# JN5168_Breakout.net
KiCad netlist of a schematic drawn in EAGLE
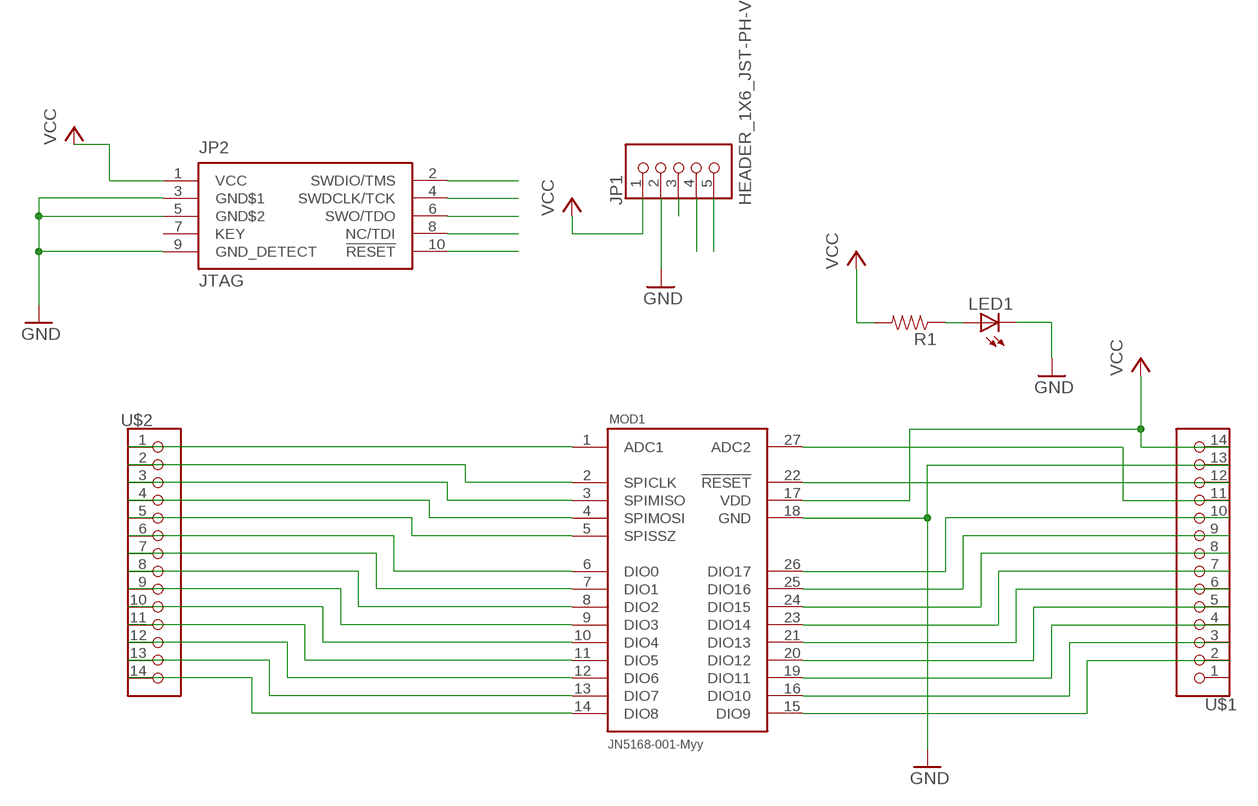
[diagram p0: schematic, sheet 1]

(export (version "E")
  (design (tool "Eeschema 10.0.6"))
  (components
    (comp (ref "JP1")
      (value "HEADER_1X6_JST-PH-V")
      (footprint "eagle-import:HEADER_100MIL_1X5")
      (libsource (lib "eagle-import") (part "HEADER_1X5100MIL_PTH"))
    )
    (comp (ref "JP2")
      (value "JTAG_HEADER")
      (footprint "eagle-import:HEADER_50MIL_2X5_PTH")
      (libsource (lib "eagle-import") (part "JTAG_HEADER"))
    )
    (comp (ref "LED1")
      (value "LEDCHIPLED_0603")
      (footprint "eagle-import:CHIPLED_0603")
      (libsource (lib "eagle-import") (part "LEDCHIPLED_0603"))
    )
    (comp (ref "MOD1")
      (value "JN5168-001-M00")
      (footprint "eagle-import:JN5168-001-M00")
      (libsource (lib "eagle-import") (part "JN5168-001-M00"))
    )
    (comp (ref "R1")
      (value "R0603")
      (footprint "eagle-import:R0603")
      (libsource (lib "eagle-import") (part "R0603"))
    )
    (comp (ref "U$1")
      (value "HEADER_1X14_100MIL_PTH")
      (footprint "eagle-import:HEADER_100MIL_1X14_PTH")
      (libsource (lib "eagle-import") (part "HEADER_1X14_100MIL_PTH"))
    )
    (comp (ref "U$2")
      (value "HEADER_1X14_100MIL_PTH")
      (footprint "eagle-import:HEADER_100MIL_1X14_PTH")
      (libsource (lib "eagle-import") (part "HEADER_1X14_100MIL_PTH"))
    )
  )
  (nets
    (net (code "1") (name "/GPIO4{slash}JTAG_TCK") (class "Default")
      (node (ref "JP2") (pin "4") (pinfunction "SWDCLK/TCK_4") (pintype "bidirectional"))
      (node (ref "MOD1") (pin "10") (pinfunction "DIO4_10") (pintype "bidirectional"))
      (node (ref "U$2") (pin "10") (pinfunction "10_10") (pintype "passive"))
    )
    (net (code "2") (name "/GPIO5{slash}JTAG_TMS") (class "Default")
      (node (ref "JP2") (pin "2") (pinfunction "SWDIO/TMS_2") (pintype "bidirectional"))
      (node (ref "MOD1") (pin "11") (pinfunction "DIO5_11") (pintype "bidirectional"))
      (node (ref "U$2") (pin "11") (pinfunction "11_11") (pintype "passive"))
    )
    (net (code "3") (name "/GPIO6{slash}TXD0{slash}JTAG_TDO") (class "Default")
      (node (ref "JP1") (pin "4") (pinfunction "4_4") (pintype "passive"))
      (node (ref "JP2") (pin "6") (pinfunction "SWO/TDO_6") (pintype "bidirectional"))
      (node (ref "MOD1") (pin "12") (pinfunction "DIO6_12") (pintype "bidirectional"))
      (node (ref "U$2") (pin "12") (pinfunction "12_12") (pintype "passive"))
    )
    (net (code "4") (name "/GPIO7{slash}RXD0{slash}JTAG_TDI") (class "Default")
      (node (ref "JP1") (pin "5") (pinfunction "5_5") (pintype "passive"))
      (node (ref "JP2") (pin "8") (pinfunction "NC/TDI_8") (pintype "bidirectional"))
      (node (ref "MOD1") (pin "13") (pinfunction "DIO7_13") (pintype "bidirectional"))
      (node (ref "U$2") (pin "13") (pinfunction "13_13") (pintype "passive"))
    )
    (net (code "5") (name "/~{RESET}") (class "Default")
      (node (ref "JP1") (pin "3") (pinfunction "3_3") (pintype "passive"))
      (node (ref "JP2") (pin "10") (pinfunction "~{RESET}_10") (pintype "bidirectional"))
      (node (ref "MOD1") (pin "22") (pinfunction "~{RESET}_22") (pintype "input"))
      (node (ref "U$1") (pin "12") (pinfunction "12_12") (pintype "passive"))
    )
    (net (code "6") (name "GND") (class "Default")
      (node (ref "JP1") (pin "2") (pinfunction "2_2") (pintype "passive"))
      (node (ref "JP2") (pin "3") (pinfunction "GND$1_3") (pintype "power_in"))
      (node (ref "JP2") (pin "5") (pinfunction "GND$2_5") (pintype "power_in"))
      (node (ref "JP2") (pin "9") (pinfunction "GND_DETECT_9") (pintype "power_in"))
      (node (ref "LED1") (pin "C") (pinfunction "C_C") (pintype "passive"))
      (node (ref "MOD1") (pin "18") (pinfunction "GND_18") (pintype "power_in"))
      (node (ref "U$1") (pin "13") (pinfunction "13_13") (pintype "passive"))
    )
    (net (code "7") (name "Net-(LED1-PadA)") (class "Default")
      (node (ref "LED1") (pin "A") (pinfunction "A_A") (pintype "passive"))
      (node (ref "R1") (pin "1") (pinfunction "1_1") (pintype "passive"))
    )
    (net (code "8") (name "Net-(MOD1-ADC1)") (class "Default")
      (node (ref "MOD1") (pin "1") (pinfunction "ADC1_1") (pintype "bidirectional"))
      (node (ref "U$2") (pin "1") (pinfunction "1_1") (pintype "passive"))
    )
    (net (code "9") (name "Net-(MOD1-ADC2)") (class "Default")
      (node (ref "MOD1") (pin "27") (pinfunction "ADC2_27") (pintype "bidirectional"))
      (node (ref "U$1") (pin "11") (pinfunction "11_11") (pintype "passive"))
    )
    (net (code "10") (name "Net-(MOD1-DIO0)") (class "Default")
      (node (ref "MOD1") (pin "6") (pinfunction "DIO0_6") (pintype "bidirectional"))
      (node (ref "U$2") (pin "6") (pinfunction "6_6") (pintype "passive"))
    )
    (net (code "11") (name "Net-(MOD1-DIO1)") (class "Default")
      (node (ref "MOD1") (pin "7") (pinfunction "DIO1_7") (pintype "bidirectional"))
      (node (ref "U$2") (pin "7") (pinfunction "7_7") (pintype "passive"))
    )
    (net (code "12") (name "Net-(MOD1-DIO2)") (class "Default")
      (node (ref "MOD1") (pin "8") (pinfunction "DIO2_8") (pintype "bidirectional"))
      (node (ref "U$2") (pin "8") (pinfunction "8_8") (pintype "passive"))
    )
    (net (code "13") (name "Net-(MOD1-DIO3)") (class "Default")
      (node (ref "MOD1") (pin "9") (pinfunction "DIO3_9") (pintype "bidirectional"))
      (node (ref "U$2") (pin "9") (pinfunction "9_9") (pintype "passive"))
    )
    (net (code "14") (name "Net-(MOD1-DIO8)") (class "Default")
      (node (ref "MOD1") (pin "14") (pinfunction "DIO8_14") (pintype "bidirectional"))
      (node (ref "U$2") (pin "14") (pinfunction "14_14") (pintype "passive"))
    )
    (net (code "15") (name "Net-(MOD1-DIO9)") (class "Default")
      (node (ref "MOD1") (pin "15") (pinfunction "DIO9_15") (pintype "bidirectional"))
      (node (ref "U$1") (pin "2") (pinfunction "2_2") (pintype "passive"))
    )
    (net (code "16") (name "Net-(MOD1-DIO10)") (class "Default")
      (node (ref "MOD1") (pin "16") (pinfunction "DIO10_16") (pintype "bidirectional"))
      (node (ref "U$1") (pin "3") (pinfunction "3_3") (pintype "passive"))
    )
    (net (code "17") (name "Net-(MOD1-DIO11)") (class "Default")
      (node (ref "MOD1") (pin "19") (pinfunction "DIO11_19") (pintype "bidirectional"))
      (node (ref "U$1") (pin "4") (pinfunction "4_4") (pintype "passive"))
    )
    (net (code "18") (name "Net-(MOD1-DIO12)") (class "Default")
      (node (ref "MOD1") (pin "20") (pinfunction "DIO12_20") (pintype "bidirectional"))
      (node (ref "U$1") (pin "5") (pinfunction "5_5") (pintype "passive"))
    )
    (net (code "19") (name "Net-(MOD1-DIO13)") (class "Default")
      (node (ref "MOD1") (pin "21") (pinfunction "DIO13_21") (pintype "bidirectional"))
      (node (ref "U$1") (pin "6") (pinfunction "6_6") (pintype "passive"))
    )
    (net (code "20") (name "Net-(MOD1-DIO14)") (class "Default")
      (node (ref "MOD1") (pin "23") (pinfunction "DIO14_23") (pintype "bidirectional"))
      (node (ref "U$1") (pin "7") (pinfunction "7_7") (pintype "passive"))
    )
    (net (code "21") (name "Net-(MOD1-DIO15)") (class "Default")
      (node (ref "MOD1") (pin "24") (pinfunction "DIO15_24") (pintype "bidirectional"))
      (node (ref "U$1") (pin "8") (pinfunction "8_8") (pintype "passive"))
    )
    (net (code "22") (name "Net-(MOD1-DIO16)") (class "Default")
      (node (ref "MOD1") (pin "25") (pinfunction "DIO16_25") (pintype "bidirectional"))
      (node (ref "U$1") (pin "9") (pinfunction "9_9") (pintype "passive"))
    )
    (net (code "23") (name "Net-(MOD1-DIO17)") (class "Default")
      (node (ref "MOD1") (pin "26") (pinfunction "DIO17_26") (pintype "bidirectional"))
      (node (ref "U$1") (pin "10") (pinfunction "10_10") (pintype "passive"))
    )
    (net (code "24") (name "Net-(MOD1-SPICLK)") (class "Default")
      (node (ref "MOD1") (pin "2") (pinfunction "SPICLK_2") (pintype "bidirectional"))
      (node (ref "U$2") (pin "2") (pinfunction "2_2") (pintype "passive"))
    )
    (net (code "25") (name "Net-(MOD1-SPIMISO)") (class "Default")
      (node (ref "MOD1") (pin "3") (pinfunction "SPIMISO_3") (pintype "bidirectional"))
      (node (ref "U$2") (pin "3") (pinfunction "3_3") (pintype "passive"))
    )
    (net (code "26") (name "Net-(MOD1-SPIMOSI)") (class "Default")
      (node (ref "MOD1") (pin "4") (pinfunction "SPIMOSI_4") (pintype "bidirectional"))
      (node (ref "U$2") (pin "4") (pinfunction "4_4") (pintype "passive"))
    )
    (net (code "27") (name "Net-(MOD1-SPISSZ)") (class "Default")
      (node (ref "MOD1") (pin "5") (pinfunction "SPISSZ_5") (pintype "bidirectional"))
      (node (ref "U$2") (pin "5") (pinfunction "5_5") (pintype "passive"))
    )
    (net (code "28") (name "VCC") (class "Default")
      (node (ref "JP1") (pin "1") (pinfunction "1_1") (pintype "passive"))
      (node (ref "JP2") (pin "1") (pinfunction "VCC_1") (pintype "power_in"))
      (node (ref "MOD1") (pin "17") (pinfunction "VDD_17") (pintype "power_in"))
      (node (ref "R1") (pin "2") (pinfunction "2_2") (pintype "passive"))
      (node (ref "U$1") (pin "14") (pinfunction "14_14") (pintype "passive"))
    )
    (net (code "29") (name "unconnected-(JP2-KEY-Pad7)") (class "Default")
      (node (ref "JP2") (pin "7") (pinfunction "KEY_7") (pintype "no_connect"))
    )
    (net (code "30") (name "unconnected-(U$1-Pad1)") (class "Default")
      (node (ref "U$1") (pin "1") (pinfunction "1_1") (pintype "passive"))
    )
  )
)
